# MinSys_MCS51.net
KiCad netlist of a schematic drawn in EAGLE
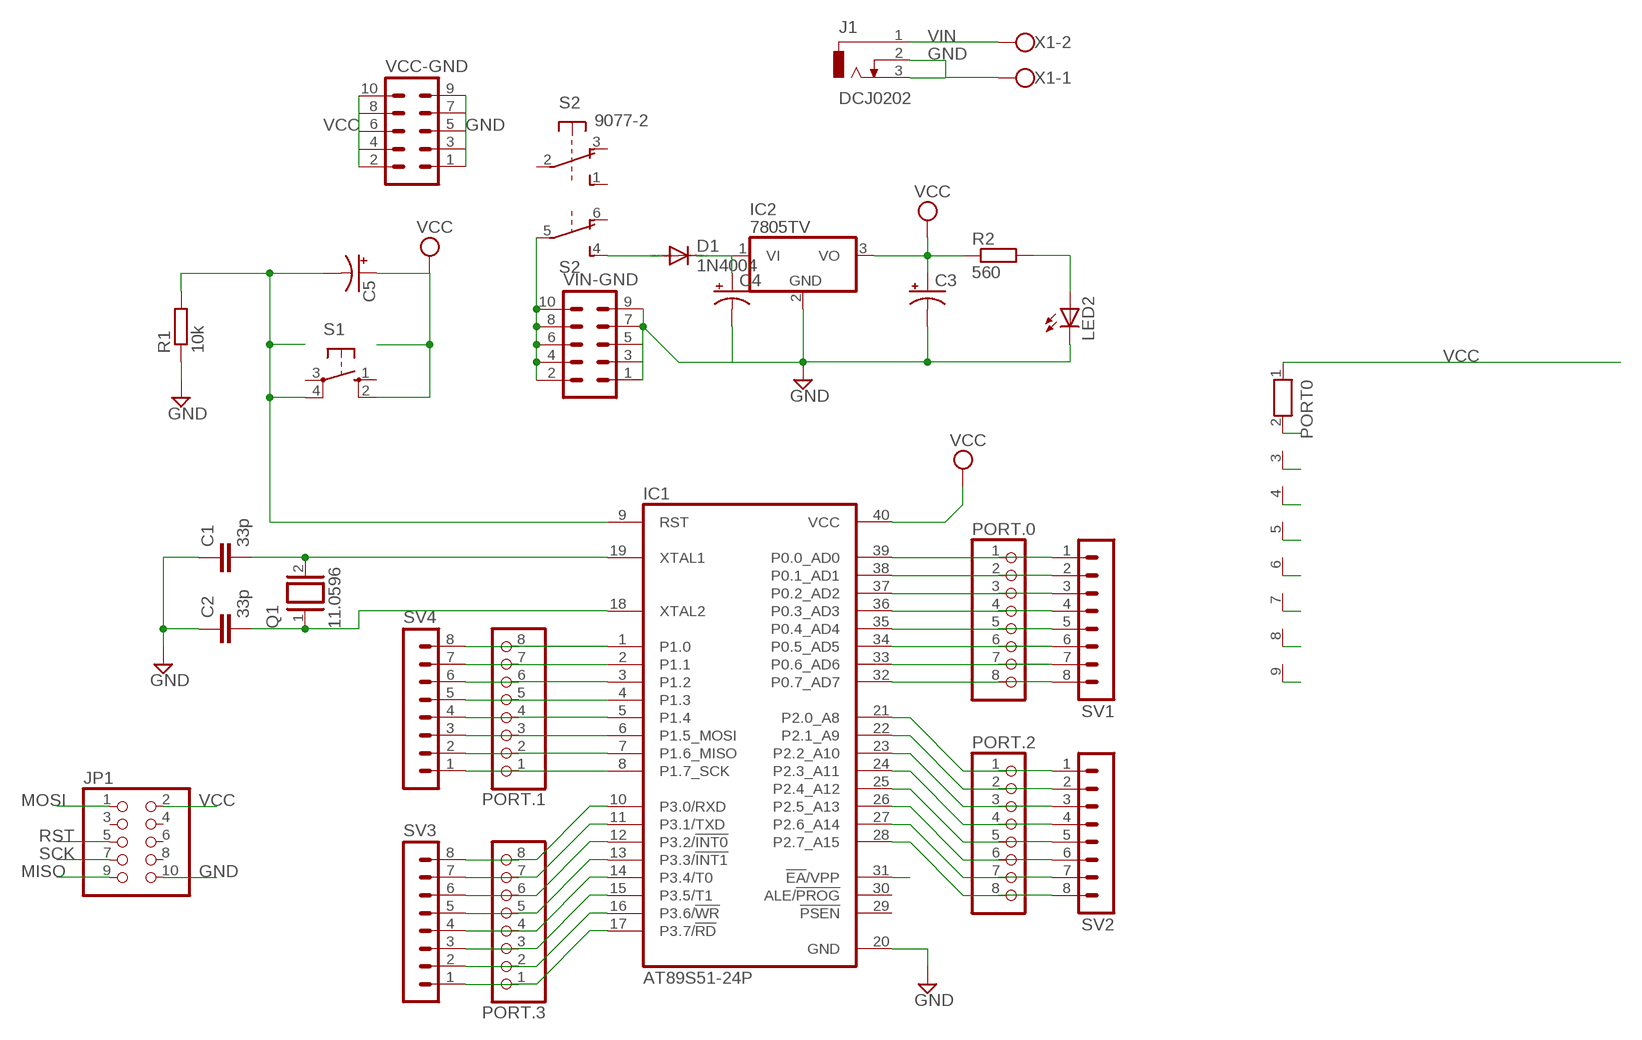
[diagram p0: schematic, sheet 1]

(export (version "E")
  (design (tool "Eeschema 10.0.6"))
  (components
    (comp (ref "C1")
      (value "33p")
      (footprint "eagle-import:C2.5-3")
      (libsource (lib "eagle-import") (part "C2,5-3"))
    )
    (comp (ref "C2")
      (value "33p")
      (footprint "eagle-import:C2.5-3")
      (libsource (lib "eagle-import") (part "C2,5-3"))
    )
    (comp (ref "C3")
      (value "CPOL-USE2,5-6E")
      (footprint "eagle-import:E2,5-6E")
      (libsource (lib "eagle-import") (part "CPOL-USE2,5-6E"))
    )
    (comp (ref "C4")
      (value "CPOL-USE2,5-6E")
      (footprint "eagle-import:E2,5-6E")
      (libsource (lib "eagle-import") (part "CPOL-USE2,5-6E"))
    )
    (comp (ref "C5")
      (value "CPOL-USE2.5-6")
      (footprint "eagle-import:E2,5-6")
      (libsource (lib "eagle-import") (part "CPOL-USE2.5-6"))
    )
    (comp (ref "D1")
      (value "1N4004")
      (footprint "eagle-import:DO41-10")
      (libsource (lib "eagle-import") (part "1N4004"))
    )
    (comp (ref "IC1")
      (value "AT89S51-24P")
      (footprint "eagle-import:DIL40")
      (fields (field (name "MPN") "AT89S51-24PU"))
      (libsource (lib "eagle-import") (part "AT89S51-P24"))
    )
    (comp (ref "IC2")
      (value "7805TV")
      (footprint "eagle-import:TO220V")
      (libsource (lib "eagle-import") (part "78TV05"))
    )
    (comp (ref "J1")
      (value "DCJ0202")
      (footprint "eagle-import:DCJ0202")
      (libsource (lib "eagle-import") (part "DCJ0202"))
    )
    (comp (ref "JP1")
      (value "PINHD-2X5")
      (footprint "eagle-import:2X05")
      (libsource (lib "eagle-import") (part "PINHD-2X5"))
    )
    (comp (ref "LED2")
      (value "LED3MM")
      (footprint "eagle-import:LED3MM")
      (libsource (lib "eagle-import") (part "LED3MM"))
    )
    (comp (ref "PORT.0")
      (value "PINHD-1X8")
      (footprint "eagle-import:1X08")
      (libsource (lib "eagle-import") (part "PINHD-1X8"))
    )
    (comp (ref "PORT.1")
      (value "PINHD-1X8")
      (footprint "eagle-import:1X08")
      (libsource (lib "eagle-import") (part "PINHD-1X8"))
    )
    (comp (ref "PORT.2")
      (value "PINHD-1X8")
      (footprint "eagle-import:1X08")
      (libsource (lib "eagle-import") (part "PINHD-1X8"))
    )
    (comp (ref "PORT.3")
      (value "PINHD-1X8")
      (footprint "eagle-import:1X08")
      (libsource (lib "eagle-import") (part "PINHD-1X8"))
    )
    (comp (ref "PORT0")
      (value "RN08")
      (footprint "eagle-import:RN-9")
      (libsource (lib "eagle-import") (part "RN08"))
    )
    (comp (ref "Q1")
      (value "11.0596")
      (footprint "eagle-import:QS")
      (libsource (lib "eagle-import") (part "XTAL/S"))
    )
    (comp (ref "R1")
      (value "10k")
      (footprint "eagle-import:0207_10")
      (libsource (lib "eagle-import") (part "R-EU_0207/10"))
    )
    (comp (ref "R2")
      (value "560")
      (footprint "eagle-import:0207_10")
      (libsource (lib "eagle-import") (part "resistor_R-EU_0207/10"))
    )
    (comp (ref "S1")
      (value "10-XX")
      (footprint "eagle-import:B3F-10XX")
      (fields (field (name "MPN") "B3F-1000"))
      (libsource (lib "eagle-import") (part "10-XX"))
    )
    (comp (ref "S2")
      (value "9077-2")
      (footprint "eagle-import:9077-2")
      (libsource (lib "eagle-import") (part "9077-2"))
    )
    (comp (ref "SV1")
      (value "MA08-1")
      (footprint "eagle-import:MA08-1")
      (libsource (lib "eagle-import") (part "MA08-1"))
    )
    (comp (ref "SV2")
      (value "MA08-1")
      (footprint "eagle-import:MA08-1")
      (libsource (lib "eagle-import") (part "MA08-1"))
    )
    (comp (ref "SV3")
      (value "MA08-1")
      (footprint "eagle-import:MA08-1")
      (libsource (lib "eagle-import") (part "MA08-1"))
    )
    (comp (ref "SV4")
      (value "MA08-1")
      (footprint "eagle-import:MA08-1")
      (libsource (lib "eagle-import") (part "MA08-1"))
    )
    (comp (ref "VCC-GND")
      (value "MA05-2")
      (footprint "eagle-import:MA05-2")
      (libsource (lib "eagle-import") (part "MA05-2"))
    )
    (comp (ref "VIN-GND")
      (value "MA05-2")
      (footprint "eagle-import:MA05-2")
      (libsource (lib "eagle-import") (part "MA05-2"))
    )
    (comp (ref "X1")
      (value "W237-102")
      (footprint "eagle-import:W237-102")
      (fields (field (name "MPN") "237-102"))
      (libsource (lib "eagle-import") (part "W237-102"))
    )
  )
  (nets
    (net (code "1") (name "/MISO") (class "Default")
      (node (ref "IC1") (pin "7") (pinfunction "P1.6_MISO_7") (pintype "bidirectional"))
      (node (ref "JP1") (pin "9") (pinfunction "9_9") (pintype "passive"))
      (node (ref "PORT.1") (pin "2") (pinfunction "2_2") (pintype "passive"))
      (node (ref "SV4") (pin "2") (pinfunction "2_2") (pintype "passive"))
    )
    (net (code "2") (name "/MOSI") (class "Default")
      (node (ref "IC1") (pin "6") (pinfunction "P1.5_MOSI_6") (pintype "bidirectional"))
      (node (ref "JP1") (pin "1") (pinfunction "1_1") (pintype "passive"))
      (node (ref "PORT.1") (pin "3") (pinfunction "3_3") (pintype "passive"))
      (node (ref "SV4") (pin "3") (pinfunction "3_3") (pintype "passive"))
    )
    (net (code "3") (name "/P00") (class "Default")
      (node (ref "IC1") (pin "39") (pinfunction "P0.0_AD0_39") (pintype "bidirectional"))
      (node (ref "PORT.0") (pin "1") (pinfunction "1_1") (pintype "passive"))
      (node (ref "PORT0") (pin "2") (pinfunction "2_2") (pintype "passive"))
      (node (ref "SV1") (pin "1") (pinfunction "1_1") (pintype "passive"))
    )
    (net (code "4") (name "/P01") (class "Default")
      (node (ref "IC1") (pin "38") (pinfunction "P0.1_AD1_38") (pintype "bidirectional"))
      (node (ref "PORT.0") (pin "2") (pinfunction "2_2") (pintype "passive"))
      (node (ref "PORT0") (pin "3") (pinfunction "3_3") (pintype "passive"))
      (node (ref "SV1") (pin "2") (pinfunction "2_2") (pintype "passive"))
    )
    (net (code "5") (name "/P02") (class "Default")
      (node (ref "IC1") (pin "37") (pinfunction "P0.2_AD2_37") (pintype "bidirectional"))
      (node (ref "PORT.0") (pin "3") (pinfunction "3_3") (pintype "passive"))
      (node (ref "PORT0") (pin "4") (pinfunction "4_4") (pintype "passive"))
      (node (ref "SV1") (pin "3") (pinfunction "3_3") (pintype "passive"))
    )
    (net (code "6") (name "/P03") (class "Default")
      (node (ref "IC1") (pin "36") (pinfunction "P0.3_AD3_36") (pintype "bidirectional"))
      (node (ref "PORT.0") (pin "4") (pinfunction "4_4") (pintype "passive"))
      (node (ref "PORT0") (pin "5") (pinfunction "5_5") (pintype "passive"))
      (node (ref "SV1") (pin "4") (pinfunction "4_4") (pintype "passive"))
    )
    (net (code "7") (name "/P04") (class "Default")
      (node (ref "IC1") (pin "35") (pinfunction "P0.4_AD4_35") (pintype "bidirectional"))
      (node (ref "PORT.0") (pin "5") (pinfunction "5_5") (pintype "passive"))
      (node (ref "PORT0") (pin "6") (pinfunction "6_6") (pintype "passive"))
      (node (ref "SV1") (pin "5") (pinfunction "5_5") (pintype "passive"))
    )
    (net (code "8") (name "/P05") (class "Default")
      (node (ref "IC1") (pin "34") (pinfunction "P0.5_AD5_34") (pintype "bidirectional"))
      (node (ref "PORT.0") (pin "6") (pinfunction "6_6") (pintype "passive"))
      (node (ref "PORT0") (pin "7") (pinfunction "7_7") (pintype "passive"))
      (node (ref "SV1") (pin "6") (pinfunction "6_6") (pintype "passive"))
    )
    (net (code "9") (name "/P06") (class "Default")
      (node (ref "IC1") (pin "33") (pinfunction "P0.6_AD6_33") (pintype "bidirectional"))
      (node (ref "PORT.0") (pin "7") (pinfunction "7_7") (pintype "passive"))
      (node (ref "PORT0") (pin "8") (pinfunction "8_8") (pintype "passive"))
      (node (ref "SV1") (pin "7") (pinfunction "7_7") (pintype "passive"))
    )
    (net (code "10") (name "/P07") (class "Default")
      (node (ref "IC1") (pin "32") (pinfunction "P0.7_AD7_32") (pintype "bidirectional"))
      (node (ref "PORT.0") (pin "8") (pinfunction "8_8") (pintype "passive"))
      (node (ref "PORT0") (pin "9") (pinfunction "9_9") (pintype "passive"))
      (node (ref "SV1") (pin "8") (pinfunction "8_8") (pintype "passive"))
    )
    (net (code "11") (name "/RST") (class "Default")
      (node (ref "C5") (pin "-") (pinfunction "-_-") (pintype "passive"))
      (node (ref "IC1") (pin "9") (pinfunction "RST_9") (pintype "input"))
      (node (ref "JP1") (pin "5") (pinfunction "5_5") (pintype "passive"))
      (node (ref "R1") (pin "2") (pinfunction "2_2") (pintype "passive"))
      (node (ref "S1") (pin "4") (pinfunction "P1_4") (pintype "passive"))
    )
    (net (code "12") (name "/SCK") (class "Default")
      (node (ref "IC1") (pin "8") (pinfunction "P1.7_SCK_8") (pintype "bidirectional"))
      (node (ref "JP1") (pin "7") (pinfunction "7_7") (pintype "passive"))
      (node (ref "PORT.1") (pin "1") (pinfunction "1_1") (pintype "passive"))
      (node (ref "SV4") (pin "1") (pinfunction "1_1") (pintype "passive"))
    )
    (net (code "13") (name "/VIN") (class "Default")
      (node (ref "J1") (pin "1") (pinfunction "1_1") (pintype "passive"))
      (node (ref "S2") (pin "5") (pinfunction "P_5") (pintype "passive"))
      (node (ref "VIN-GND") (pin "10") (pinfunction "10_10") (pintype "passive"))
      (node (ref "VIN-GND") (pin "2") (pinfunction "2_2") (pintype "passive"))
      (node (ref "VIN-GND") (pin "4") (pinfunction "4_4") (pintype "passive"))
      (node (ref "VIN-GND") (pin "6") (pinfunction "6_6") (pintype "passive"))
      (node (ref "VIN-GND") (pin "8") (pinfunction "8_8") (pintype "passive"))
      (node (ref "X1") (pin "2") (pinfunction "KL_2") (pintype "passive"))
    )
    (net (code "14") (name "GND") (class "Default")
      (node (ref "C1") (pin "1") (pinfunction "1_1") (pintype "passive"))
      (node (ref "C2") (pin "1") (pinfunction "1_1") (pintype "passive"))
      (node (ref "C3") (pin "-") (pinfunction "-_-") (pintype "passive"))
      (node (ref "C4") (pin "-") (pinfunction "-_-") (pintype "passive"))
      (node (ref "IC1") (pin "20") (pinfunction "GND_20") (pintype "power_in"))
      (node (ref "IC2") (pin "2") (pinfunction "GND_2") (pintype "passive"))
      (node (ref "J1") (pin "2") (pinfunction "2_2") (pintype "passive"))
      (node (ref "J1") (pin "3") (pinfunction "3_3") (pintype "passive"))
      (node (ref "JP1") (pin "10") (pinfunction "10_10") (pintype "passive"))
      (node (ref "LED2") (pin "K") (pinfunction "C_K") (pintype "passive"))
      (node (ref "R1") (pin "1") (pinfunction "1_1") (pintype "passive"))
      (node (ref "VCC-GND") (pin "1") (pinfunction "1_1") (pintype "passive"))
      (node (ref "VCC-GND") (pin "3") (pinfunction "3_3") (pintype "passive"))
      (node (ref "VCC-GND") (pin "5") (pinfunction "5_5") (pintype "passive"))
      (node (ref "VCC-GND") (pin "7") (pinfunction "7_7") (pintype "passive"))
      (node (ref "VCC-GND") (pin "9") (pinfunction "9_9") (pintype "passive"))
      (node (ref "VIN-GND") (pin "1") (pinfunction "1_1") (pintype "passive"))
      (node (ref "VIN-GND") (pin "3") (pinfunction "3_3") (pintype "passive"))
      (node (ref "VIN-GND") (pin "5") (pinfunction "5_5") (pintype "passive"))
      (node (ref "VIN-GND") (pin "7") (pinfunction "7_7") (pintype "passive"))
      (node (ref "VIN-GND") (pin "9") (pinfunction "9_9") (pintype "passive"))
      (node (ref "X1") (pin "1") (pinfunction "KL_1") (pintype "passive"))
    )
    (net (code "15") (name "Net-(IC1-P1.0)") (class "Default")
      (node (ref "IC1") (pin "1") (pinfunction "P1.0_1") (pintype "bidirectional"))
      (node (ref "PORT.1") (pin "8") (pinfunction "8_8") (pintype "passive"))
      (node (ref "SV4") (pin "8") (pinfunction "8_8") (pintype "passive"))
    )
    (net (code "16") (name "Net-(IC1-P1.1)") (class "Default")
      (node (ref "IC1") (pin "2") (pinfunction "P1.1_2") (pintype "bidirectional"))
      (node (ref "PORT.1") (pin "7") (pinfunction "7_7") (pintype "passive"))
      (node (ref "SV4") (pin "7") (pinfunction "7_7") (pintype "passive"))
    )
    (net (code "17") (name "Net-(IC1-P1.2)") (class "Default")
      (node (ref "IC1") (pin "3") (pinfunction "P1.2_3") (pintype "bidirectional"))
      (node (ref "PORT.1") (pin "6") (pinfunction "6_6") (pintype "passive"))
      (node (ref "SV4") (pin "6") (pinfunction "6_6") (pintype "passive"))
    )
    (net (code "18") (name "Net-(IC1-P1.3)") (class "Default")
      (node (ref "IC1") (pin "4") (pinfunction "P1.3_4") (pintype "bidirectional"))
      (node (ref "PORT.1") (pin "5") (pinfunction "5_5") (pintype "passive"))
      (node (ref "SV4") (pin "5") (pinfunction "5_5") (pintype "passive"))
    )
    (net (code "19") (name "Net-(IC1-P1.4)") (class "Default")
      (node (ref "IC1") (pin "5") (pinfunction "P1.4_5") (pintype "bidirectional"))
      (node (ref "PORT.1") (pin "4") (pinfunction "4_4") (pintype "passive"))
      (node (ref "SV4") (pin "4") (pinfunction "4_4") (pintype "passive"))
    )
    (net (code "20") (name "Net-(IC1-P2.0_A8)") (class "Default")
      (node (ref "IC1") (pin "21") (pinfunction "P2.0_A8_21") (pintype "bidirectional"))
      (node (ref "PORT.2") (pin "1") (pinfunction "1_1") (pintype "passive"))
      (node (ref "SV2") (pin "1") (pinfunction "1_1") (pintype "passive"))
    )
    (net (code "21") (name "Net-(IC1-P2.1_A9)") (class "Default")
      (node (ref "IC1") (pin "22") (pinfunction "P2.1_A9_22") (pintype "bidirectional"))
      (node (ref "PORT.2") (pin "2") (pinfunction "2_2") (pintype "passive"))
      (node (ref "SV2") (pin "2") (pinfunction "2_2") (pintype "passive"))
    )
    (net (code "22") (name "Net-(IC1-P2.2_A10)") (class "Default")
      (node (ref "IC1") (pin "23") (pinfunction "P2.2_A10_23") (pintype "bidirectional"))
      (node (ref "PORT.2") (pin "3") (pinfunction "3_3") (pintype "passive"))
      (node (ref "SV2") (pin "3") (pinfunction "3_3") (pintype "passive"))
    )
    (net (code "23") (name "Net-(IC1-P2.3_A11)") (class "Default")
      (node (ref "IC1") (pin "24") (pinfunction "P2.3_A11_24") (pintype "bidirectional"))
      (node (ref "PORT.2") (pin "4") (pinfunction "4_4") (pintype "passive"))
      (node (ref "SV2") (pin "4") (pinfunction "4_4") (pintype "passive"))
    )
    (net (code "24") (name "Net-(IC1-P2.4_A12)") (class "Default")
      (node (ref "IC1") (pin "25") (pinfunction "P2.4_A12_25") (pintype "bidirectional"))
      (node (ref "PORT.2") (pin "5") (pinfunction "5_5") (pintype "passive"))
      (node (ref "SV2") (pin "5") (pinfunction "5_5") (pintype "passive"))
    )
    (net (code "25") (name "Net-(IC1-P2.5_A13)") (class "Default")
      (node (ref "IC1") (pin "26") (pinfunction "P2.5_A13_26") (pintype "bidirectional"))
      (node (ref "PORT.2") (pin "6") (pinfunction "6_6") (pintype "passive"))
      (node (ref "SV2") (pin "6") (pinfunction "6_6") (pintype "passive"))
    )
    (net (code "26") (name "Net-(IC1-P2.6_A14)") (class "Default")
      (node (ref "IC1") (pin "27") (pinfunction "P2.6_A14_27") (pintype "bidirectional"))
      (node (ref "PORT.2") (pin "7") (pinfunction "7_7") (pintype "passive"))
      (node (ref "SV2") (pin "7") (pinfunction "7_7") (pintype "passive"))
    )
    (net (code "27") (name "Net-(IC1-P2.7_A15)") (class "Default")
      (node (ref "IC1") (pin "28") (pinfunction "P2.7_A15_28") (pintype "bidirectional"))
      (node (ref "PORT.2") (pin "8") (pinfunction "8_8") (pintype "passive"))
      (node (ref "SV2") (pin "8") (pinfunction "8_8") (pintype "passive"))
    )
    (net (code "28") (name "Net-(IC1-P3.0{slash}RXD)") (class "Default")
      (node (ref "IC1") (pin "10") (pinfunction "P3.0/RXD_10") (pintype "bidirectional"))
      (node (ref "PORT.3") (pin "8") (pinfunction "8_8") (pintype "passive"))
      (node (ref "SV3") (pin "8") (pinfunction "8_8") (pintype "passive"))
    )
    (net (code "29") (name "Net-(IC1-P3.1{slash}TXD)") (class "Default")
      (node (ref "IC1") (pin "11") (pinfunction "P3.1/TXD_11") (pintype "bidirectional"))
      (node (ref "PORT.3") (pin "7") (pinfunction "7_7") (pintype "passive"))
      (node (ref "SV3") (pin "7") (pinfunction "7_7") (pintype "passive"))
    )
    (net (code "30") (name "Net-(IC1-P3.2{slash}~{INT0})") (class "Default")
      (node (ref "IC1") (pin "12") (pinfunction "P3.2/~{INT0}_12") (pintype "bidirectional"))
      (node (ref "PORT.3") (pin "6") (pinfunction "6_6") (pintype "passive"))
      (node (ref "SV3") (pin "6") (pinfunction "6_6") (pintype "passive"))
    )
    (net (code "31") (name "Net-(IC1-P3.3{slash}~{INT1})") (class "Default")
      (node (ref "IC1") (pin "13") (pinfunction "P3.3/~{INT1}_13") (pintype "bidirectional"))
      (node (ref "PORT.3") (pin "5") (pinfunction "5_5") (pintype "passive"))
      (node (ref "SV3") (pin "5") (pinfunction "5_5") (pintype "passive"))
    )
    (net (code "32") (name "Net-(IC1-P3.4{slash}T0)") (class "Default")
      (node (ref "IC1") (pin "14") (pinfunction "P3.4/T0_14") (pintype "bidirectional"))
      (node (ref "PORT.3") (pin "4") (pinfunction "4_4") (pintype "passive"))
      (node (ref "SV3") (pin "4") (pinfunction "4_4") (pintype "passive"))
    )
    (net (code "33") (name "Net-(IC1-P3.5{slash}T1)") (class "Default")
      (node (ref "IC1") (pin "15") (pinfunction "P3.5/T1_15") (pintype "bidirectional"))
      (node (ref "PORT.3") (pin "3") (pinfunction "3_3") (pintype "passive"))
      (node (ref "SV3") (pin "3") (pinfunction "3_3") (pintype "passive"))
    )
    (net (code "34") (name "Net-(IC1-P3.6{slash}~{WR})") (class "Default")
      (node (ref "IC1") (pin "16") (pinfunction "P3.6/~{WR}_16") (pintype "bidirectional"))
      (node (ref "PORT.3") (pin "2") (pinfunction "2_2") (pintype "passive"))
      (node (ref "SV3") (pin "2") (pinfunction "2_2") (pintype "passive"))
    )
    (net (code "35") (name "Net-(IC1-P3.7{slash}~{RD})") (class "Default")
      (node (ref "IC1") (pin "17") (pinfunction "P3.7/~{RD}_17") (pintype "bidirectional"))
      (node (ref "PORT.3") (pin "1") (pinfunction "1_1") (pintype "passive"))
      (node (ref "SV3") (pin "1") (pinfunction "1_1") (pintype "passive"))
    )
    (net (code "36") (name "Net-(IC1-XTAL1)") (class "Default")
      (node (ref "C1") (pin "2") (pinfunction "2_2") (pintype "passive"))
      (node (ref "IC1") (pin "19") (pinfunction "XTAL1_19") (pintype "input"))
      (node (ref "Q1") (pin "2") (pinfunction "2_2") (pintype "passive"))
    )
    (net (code "37") (name "Net-(IC1-XTAL2)") (class "Default")
      (node (ref "C2") (pin "2") (pinfunction "2_2") (pintype "passive"))
      (node (ref "IC1") (pin "18") (pinfunction "XTAL2_18") (pintype "input"))
      (node (ref "Q1") (pin "1") (pinfunction "1_1") (pintype "passive"))
    )
    (net (code "38") (name "Net-(IC2-VI)") (class "Default")
      (node (ref "C4") (pin "+") (pinfunction "+_+") (pintype "passive"))
      (node (ref "D1") (pin "C") (pinfunction "C_C") (pintype "passive"))
      (node (ref "IC2") (pin "1") (pinfunction "VI_1") (pintype "input"))
    )
    (net (code "39") (name "Net-(LED2-PadA)") (class "Default")
      (node (ref "LED2") (pin "A") (pinfunction "A_A") (pintype "passive"))
      (node (ref "R2") (pin "2") (pinfunction "2_2") (pintype "passive"))
    )
    (net (code "40") (name "Net-(S2B-S)") (class "Default")
      (node (ref "D1") (pin "A") (pinfunction "A_A") (pintype "passive"))
      (node (ref "S2") (pin "4") (pinfunction "S_4") (pintype "passive"))
    )
    (net (code "41") (name "VCC") (class "Default")
      (node (ref "C3") (pin "+") (pinfunction "+_+") (pintype "passive"))
      (node (ref "C5") (pin "+") (pinfunction "+_+") (pintype "passive"))
      (node (ref "IC1") (pin "31") (pinfunction "~{EA}/VPP_31") (pintype "input"))
      (node (ref "IC1") (pin "40") (pinfunction "VCC_40") (pintype "power_in"))
      (node (ref "IC2") (pin "3") (pinfunction "VO_3") (pintype "passive"))
      (node (ref "JP1") (pin "2") (pinfunction "2_2") (pintype "passive"))
      (node (ref "PORT0") (pin "1") (pinfunction "1_1") (pintype "passive"))
      (node (ref "R2") (pin "1") (pinfunction "1_1") (pintype "passive"))
      (node (ref "S1") (pin "2") (pinfunction "S1_2") (pintype "passive"))
      (node (ref "VCC-GND") (pin "10") (pinfunction "10_10") (pintype "passive"))
      (node (ref "VCC-GND") (pin "2") (pinfunction "2_2") (pintype "passive"))
      (node (ref "VCC-GND") (pin "4") (pinfunction "4_4") (pintype "passive"))
      (node (ref "VCC-GND") (pin "6") (pinfunction "6_6") (pintype "passive"))
      (node (ref "VCC-GND") (pin "8") (pinfunction "8_8") (pintype "passive"))
    )
    (net (code "42") (name "unconnected-(IC1-ALE{slash}~{PROG}-Pad30)") (class "Default")
      (node (ref "IC1") (pin "30") (pinfunction "ALE/~{PROG}_30") (pintype "output"))
    )
    (net (code "43") (name "unconnected-(IC1-~{PSEN}-Pad29)") (class "Default")
      (node (ref "IC1") (pin "29") (pinfunction "~{PSEN}_29") (pintype "output"))
    )
    (net (code "44") (name "unconnected-(JP1-Pad3)") (class "Default")
      (node (ref "JP1") (pin "3") (pinfunction "3_3") (pintype "passive"))
    )
    (net (code "45") (name "unconnected-(JP1-Pad4)") (class "Default")
      (node (ref "JP1") (pin "4") (pinfunction "4_4") (pintype "passive"))
    )
    (net (code "46") (name "unconnected-(JP1-Pad6)") (class "Default")
      (node (ref "JP1") (pin "6") (pinfunction "6_6") (pintype "passive"))
    )
    (net (code "47") (name "unconnected-(JP1-Pad8)") (class "Default")
      (node (ref "JP1") (pin "8") (pinfunction "8_8") (pintype "passive"))
    )
    (net (code "48") (name "unconnected-(S1-P-Pad3)") (class "Default")
      (node (ref "S1") (pin "3") (pinfunction "P_3") (pintype "passive"))
    )
    (net (code "49") (name "unconnected-(S1-S-Pad1)") (class "Default")
      (node (ref "S1") (pin "1") (pinfunction "S_1") (pintype "passive"))
    )
    (net (code "50") (name "unconnected-(S2A-O-Pad3)") (class "Default")
      (node (ref "S2") (pin "3") (pinfunction "O_3") (pintype "passive"))
    )
    (net (code "51") (name "unconnected-(S2A-P-Pad2)") (class "Default")
      (node (ref "S2") (pin "2") (pinfunction "P_2") (pintype "passive"))
    )
    (net (code "52") (name "unconnected-(S2A-S-Pad1)") (class "Default")
      (node (ref "S2") (pin "1") (pinfunction "S_1") (pintype "passive"))
    )
    (net (code "53") (name "unconnected-(S2B-O-Pad6)") (class "Default")
      (node (ref "S2") (pin "6") (pinfunction "O_6") (pintype "passive"))
    )
  )
)
